# DO_EZO_1.net
KiCad netlist of a schematic drawn in Altium Designer
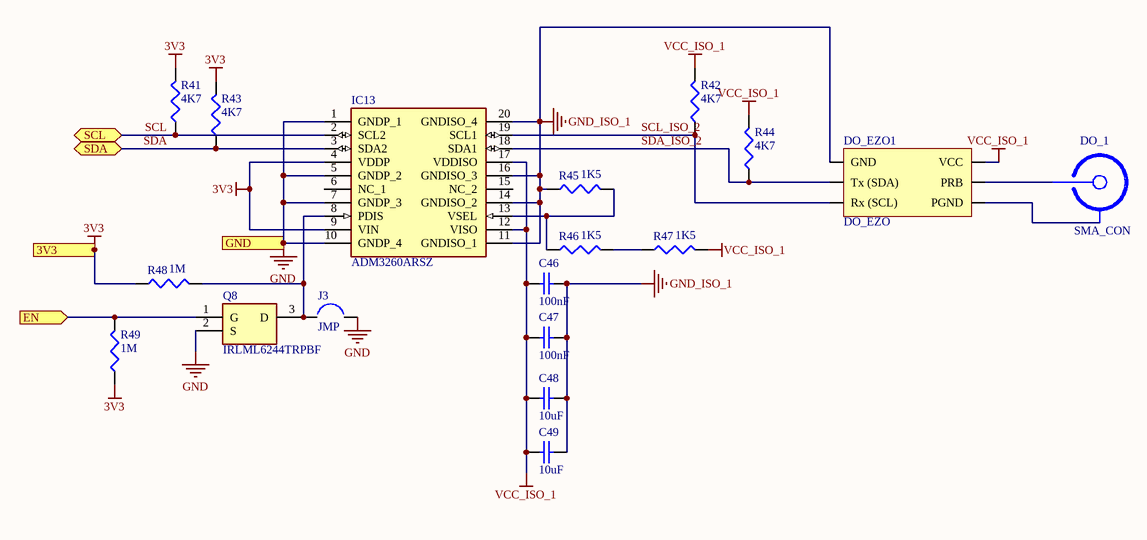
[diagram p0: DO_EZO_1.SchDoc]

(export (version "E")
  (design (tool "Eeschema 10.0.6"))
  (components
    (comp (ref "C46")
      (value "100nF")
      (footprint "1608[0603]")
      (description "Capacitor (Semiconductor SIM Model)")
      (fields (field (name "PUBLISHER") "Altium Limited"))
      (libsource (lib "Miscellaneous Devices") (part "Cap Semi"))
    )
    (comp (ref "C47")
      (value "100nF")
      (footprint "1608[0603]")
      (description "Capacitor (Semiconductor SIM Model)")
      (fields (field (name "PUBLISHER") "Altium Limited"))
      (libsource (lib "Miscellaneous Devices") (part "Cap Semi"))
    )
    (comp (ref "C48")
      (value "10uF")
      (footprint "1608[0603]")
      (description "Capacitor (Semiconductor SIM Model)")
      (fields (field (name "PUBLISHER") "Altium Limited"))
      (libsource (lib "Miscellaneous Devices") (part "Cap Semi"))
    )
    (comp (ref "C49")
      (value "10uF")
      (footprint "1608[0603]")
      (description "Capacitor (Semiconductor SIM Model)")
      (fields (field (name "PUBLISHER") "Altium Limited"))
      (libsource (lib "Miscellaneous Devices") (part "Cap Semi"))
    )
    (comp (ref "DO_1")
      (value "SMA_CON")
      (footprint "SamacSys:PCBSMAFRAHT")
      (description "Connector")
      (fields
        (field (name "MANUFACTURER_PART_NUMBER") "PCB.SMAFRA.HT")
        (field (name "MOUSER PART NUMBER") "960-PCB.SMAFRA.HT")
      )
      (libsource (lib "SamacSys") (part "SMA"))
    )
    (comp (ref "DO_EZO1") (value "DO_EZO") (footprint "DO_EZO") (libsource (lib "SamacSys") (part "DO_EZO")))
    (comp (ref "IC13")
      (value "ADM3260ARSZ")
      (footprint "SOP65P780X200-20N")
      (description "Integrated Circuit")
      (fields
        (field (name "MOUSER PART NUMBER") "584-ADM3260ARSZ")
        (field (name "RS PART NUMBER") "8319113P")
      )
      (libsource (lib "SamacSys") (part "ADM3260ARSZ"))
    )
    (comp (ref "J3") (value "JMP") (footprint "Jumper") (libsource (lib "SamacSys") (part "JMP")))
    (comp (ref "Q8")
      (value "IRLML6244TRPBF")
      (footprint "SOT95P237X112-3N")
      (description "Transistor")
      (fields
        (field (name "MOUSER PART NUMBER") "942-IRLML6244TRPBF")
        (field (name "RS PART NUMBER") "7377228P")
      )
      (libsource (lib "SamacSys") (part "IRLML6244TRPBF"))
    )
    (comp (ref "R41")
      (value "4K7")
      (footprint "J1-0603")
      (description "Resistor")
      (fields (field (name "PUBLISHER") "Altium Limited"))
      (libsource (lib "Miscellaneous Devices") (part "Res3"))
    )
    (comp (ref "R42")
      (value "4K7")
      (footprint "J1-0603")
      (description "Resistor")
      (fields (field (name "PUBLISHER") "Altium Limited"))
      (libsource (lib "Miscellaneous Devices") (part "Res3"))
    )
    (comp (ref "R43")
      (value "4K7")
      (footprint "J1-0603")
      (description "Resistor")
      (fields (field (name "PUBLISHER") "Altium Limited"))
      (libsource (lib "Miscellaneous Devices") (part "Res3"))
    )
    (comp (ref "R44")
      (value "4K7")
      (footprint "J1-0603")
      (description "Resistor")
      (fields (field (name "PUBLISHER") "Altium Limited"))
      (libsource (lib "Miscellaneous Devices") (part "Res3"))
    )
    (comp (ref "R45")
      (value "1K5")
      (footprint "J1-0603")
      (description "Resistor")
      (fields (field (name "PUBLISHER") "Altium Limited"))
      (libsource (lib "Miscellaneous Devices") (part "Res3"))
    )
    (comp (ref "R46")
      (value "1K5")
      (footprint "J1-0603")
      (description "Resistor")
      (fields (field (name "PUBLISHER") "Altium Limited"))
      (libsource (lib "Miscellaneous Devices") (part "Res3"))
    )
    (comp (ref "R47")
      (value "1K5")
      (footprint "J1-0603")
      (description "Resistor")
      (fields (field (name "PUBLISHER") "Altium Limited"))
      (libsource (lib "Miscellaneous Devices") (part "Res3"))
    )
    (comp (ref "R48")
      (value "1M")
      (footprint "J1-0603")
      (description "Resistor")
      (fields (field (name "PUBLISHER") "Altium Limited"))
      (libsource (lib "Miscellaneous Devices") (part "Res3"))
    )
    (comp (ref "R49")
      (value "1M")
      (footprint "J1-0603")
      (description "Resistor")
      (fields (field (name "PUBLISHER") "Altium Limited"))
      (libsource (lib "Miscellaneous Devices") (part "Res3"))
    )
  )
  (nets
    (net (code "1") (name "/EN") (class "Default")
      (node (ref "Q8") (pin "1") (pinfunction "G_1") (pintype "passive"))
      (node (ref "R49") (pin "2") (pinfunction "2_2") (pintype "passive"))
    )
    (net (code "2") (name "/SCL") (class "Default")
      (node (ref "IC13") (pin "2") (pinfunction "SCL2_2") (pintype "bidirectional"))
      (node (ref "R41") (pin "1") (pinfunction "1_1") (pintype "passive"))
    )
    (net (code "3") (name "/SCL_ISO_2") (class "Default")
      (node (ref "DO_EZO1") (pin "3") (pinfunction "Rx_(SCL)_3") (pintype "passive"))
      (node (ref "IC13") (pin "19") (pinfunction "SCL1_19") (pintype "bidirectional"))
      (node (ref "R42") (pin "1") (pinfunction "1_1") (pintype "passive"))
    )
    (net (code "4") (name "/SDA") (class "Default")
      (node (ref "IC13") (pin "3") (pinfunction "SDA2_3") (pintype "bidirectional"))
      (node (ref "R43") (pin "1") (pinfunction "1_1") (pintype "passive"))
    )
    (net (code "5") (name "/SDA_ISO_2") (class "Default")
      (node (ref "DO_EZO1") (pin "2") (pinfunction "Tx_(SDA)_2") (pintype "passive"))
      (node (ref "IC13") (pin "18") (pinfunction "SDA1_18") (pintype "bidirectional"))
      (node (ref "R44") (pin "1") (pinfunction "1_1") (pintype "passive"))
    )
    (net (code "6") (name "3V3") (class "Default")
      (node (ref "IC13") (pin "4") (pinfunction "VDDP_4") (pintype "power_in"))
      (node (ref "IC13") (pin "9") (pinfunction "VIN_9") (pintype "power_in"))
      (node (ref "R41") (pin "2") (pinfunction "2_2") (pintype "passive"))
      (node (ref "R43") (pin "2") (pinfunction "2_2") (pintype "passive"))
      (node (ref "R48") (pin "1") (pinfunction "1_1") (pintype "passive"))
      (node (ref "R49") (pin "1") (pinfunction "1_1") (pintype "passive"))
    )
    (net (code "7") (name "GND") (class "Default")
      (node (ref "IC13") (pin "1") (pinfunction "GNDP_1_1") (pintype "power_in"))
      (node (ref "IC13") (pin "10") (pinfunction "GNDP_4_10") (pintype "power_in"))
      (node (ref "IC13") (pin "5") (pinfunction "GNDP_2_5") (pintype "power_in"))
      (node (ref "IC13") (pin "7") (pinfunction "GNDP_3_7") (pintype "power_in"))
      (node (ref "J3") (pin "2") (pinfunction "2_2") (pintype "passive"))
      (node (ref "Q8") (pin "2") (pinfunction "S_2") (pintype "passive"))
    )
    (net (code "8") (name "GND_ISO_1") (class "Default")
      (node (ref "C46") (pin "2") (pinfunction "2_2") (pintype "passive"))
      (node (ref "C47") (pin "2") (pinfunction "2_2") (pintype "passive"))
      (node (ref "C48") (pin "2") (pinfunction "2_2") (pintype "passive"))
      (node (ref "C49") (pin "2") (pinfunction "2_2") (pintype "passive"))
      (node (ref "DO_EZO1") (pin "1") (pinfunction "GND_1") (pintype "passive"))
      (node (ref "IC13") (pin "11") (pinfunction "GNDISO_1_11") (pintype "power_in"))
      (node (ref "IC13") (pin "14") (pinfunction "GNDISO_2_14") (pintype "power_in"))
      (node (ref "IC13") (pin "16") (pinfunction "GNDISO_3_16") (pintype "power_in"))
      (node (ref "IC13") (pin "20") (pinfunction "GNDISO_4_20") (pintype "power_in"))
      (node (ref "R45") (pin "1") (pinfunction "1_1") (pintype "passive"))
    )
    (net (code "9") (name "Net-(DO_EZO1-PGND)") (class "Default")
      (node (ref "DO_1") (pin "2") (pintype "passive"))
      (node (ref "DO_EZO1") (pin "6") (pinfunction "PGND_6") (pintype "passive"))
    )
    (net (code "10") (name "Net-(DO_EZO1-PRB)") (class "Default")
      (node (ref "DO_1") (pin "1") (pintype "passive"))
      (node (ref "DO_EZO1") (pin "5") (pinfunction "PRB_5") (pintype "passive"))
    )
    (net (code "11") (name "Net-(IC13-PDIS)") (class "Default")
      (node (ref "IC13") (pin "8") (pinfunction "PDIS_8") (pintype "input"))
      (node (ref "J3") (pin "1") (pinfunction "1_1") (pintype "passive"))
      (node (ref "Q8") (pin "3") (pinfunction "D_3") (pintype "passive"))
      (node (ref "R48") (pin "2") (pinfunction "2_2") (pintype "passive"))
    )
    (net (code "12") (name "Net-(IC13-VSEL)") (class "Default")
      (node (ref "IC13") (pin "13") (pinfunction "VSEL_13") (pintype "input"))
      (node (ref "R45") (pin "2") (pinfunction "2_2") (pintype "passive"))
      (node (ref "R46") (pin "1") (pinfunction "1_1") (pintype "passive"))
    )
    (net (code "13") (name "Net-(R46-Pad2)") (class "Default")
      (node (ref "R46") (pin "2") (pinfunction "2_2") (pintype "passive"))
      (node (ref "R47") (pin "1") (pinfunction "1_1") (pintype "passive"))
    )
    (net (code "14") (name "VCC_ISO_1") (class "Default")
      (node (ref "C46") (pin "1") (pinfunction "1_1") (pintype "passive"))
      (node (ref "C47") (pin "1") (pinfunction "1_1") (pintype "passive"))
      (node (ref "C48") (pin "1") (pinfunction "1_1") (pintype "passive"))
      (node (ref "C49") (pin "1") (pinfunction "1_1") (pintype "passive"))
      (node (ref "DO_EZO1") (pin "4") (pinfunction "VCC_4") (pintype "passive"))
      (node (ref "IC13") (pin "12") (pinfunction "VISO_12") (pintype "power_in"))
      (node (ref "IC13") (pin "17") (pinfunction "VDDISO_17") (pintype "power_in"))
      (node (ref "R42") (pin "2") (pinfunction "2_2") (pintype "passive"))
      (node (ref "R44") (pin "2") (pinfunction "2_2") (pintype "passive"))
      (node (ref "R47") (pin "2") (pinfunction "2_2") (pintype "passive"))
    )
    (net (code "15") (name "unconnected-(IC13-NC_1-Pad6)") (class "Default")
      (node (ref "IC13") (pin "6") (pinfunction "NC_1_6") (pintype "passive"))
    )
    (net (code "16") (name "unconnected-(IC13-NC_2-Pad15)") (class "Default")
      (node (ref "IC13") (pin "15") (pinfunction "NC_2_15") (pintype "passive"))
    )
  )
)
